# osuar_pdb.net
KiCad netlist of a schematic drawn in EAGLE
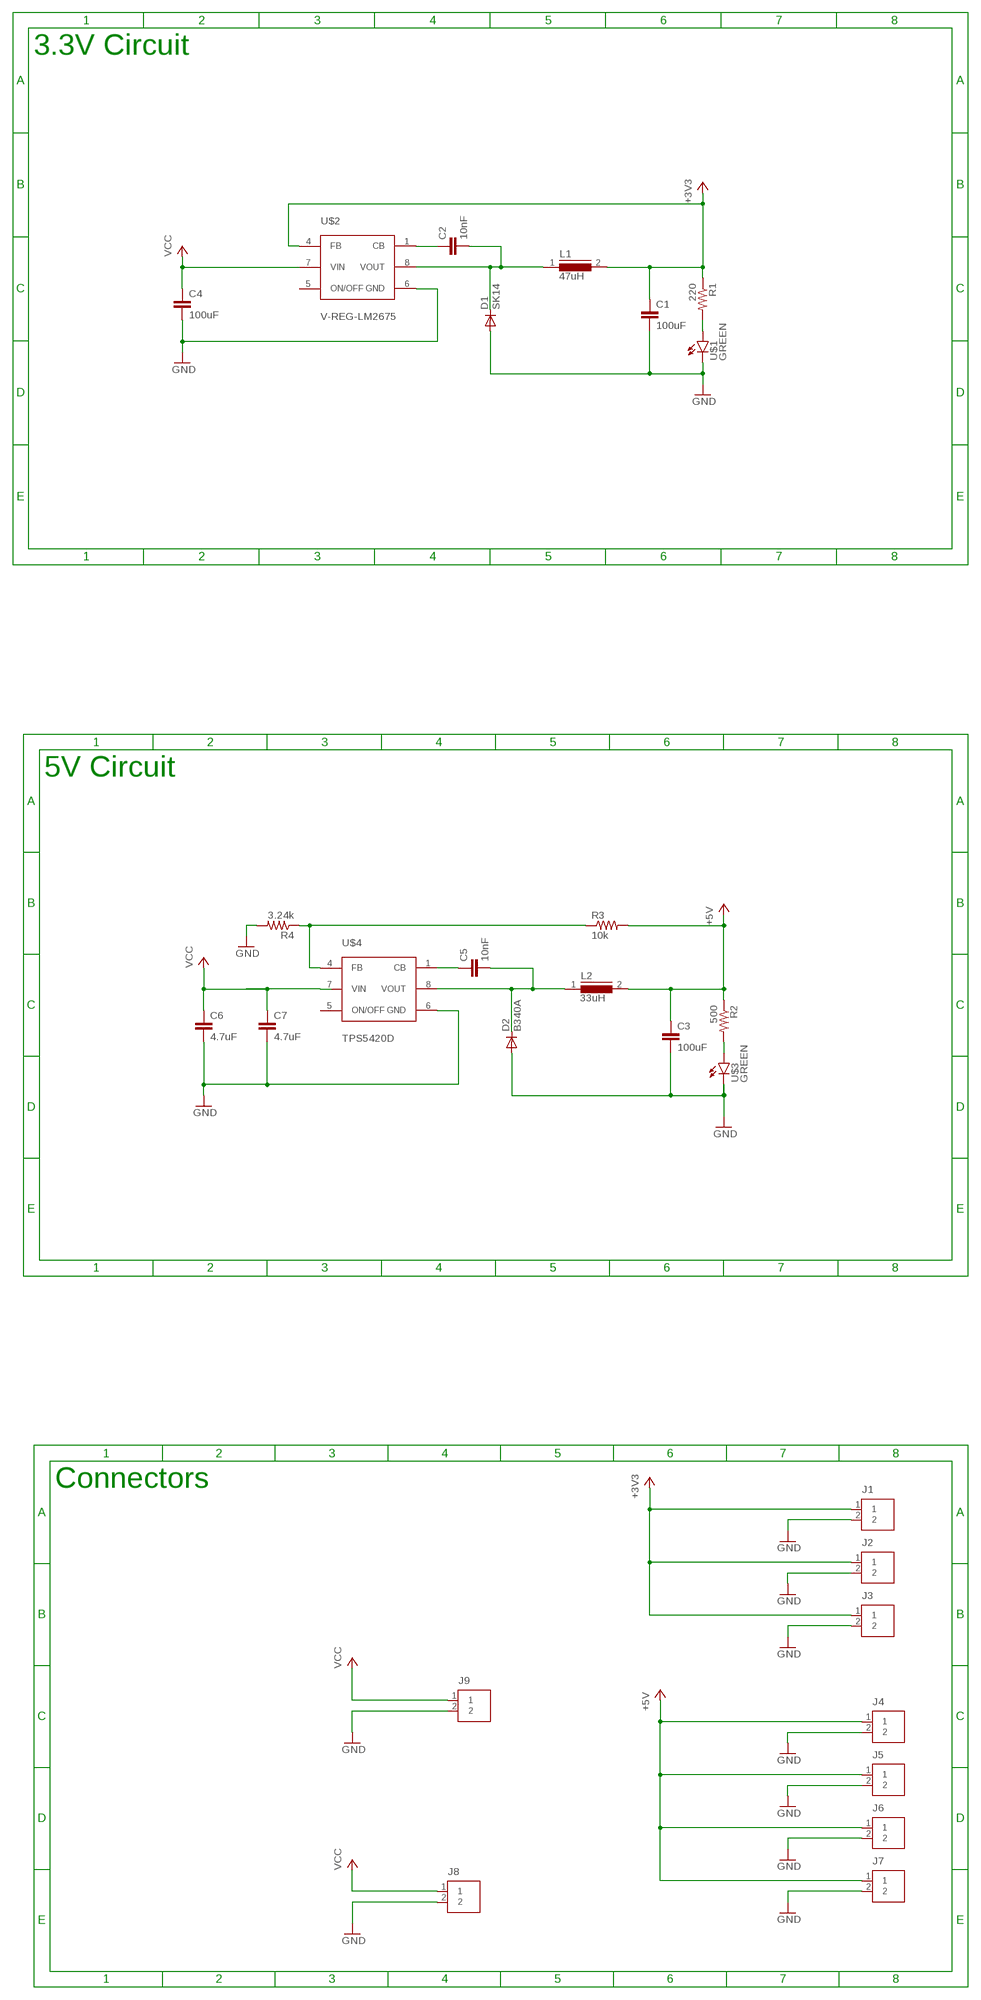
[diagram p0: schematic, sheet 1]

(export (version "E")
  (design (tool "Eeschema 10.0.6"))
  (components
    (comp (ref "C1")
      (value "100uF")
      (footprint "eagle-import:0805")
      (libsource (lib "eagle-import") (part "CAP-10UF-10V-10%(0805)"))
    )
    (comp (ref "C2")
      (value "10nF")
      (footprint "eagle-import:0603")
      (libsource (lib "eagle-import") (part "CAP-10NF-50V-10%(0603)"))
    )
    (comp (ref "C3")
      (value "100uF")
      (footprint "eagle-import:0805")
      (libsource (lib "eagle-import") (part "CAP-10UF-10V-10%(0805)"))
    )
    (comp (ref "C4")
      (value "100uF")
      (footprint "eagle-import:0805")
      (libsource (lib "eagle-import") (part "CAP-10UF-10V-10%(0805)"))
    )
    (comp (ref "C5")
      (value "10nF")
      (footprint "eagle-import:0603")
      (libsource (lib "eagle-import") (part "CAP-10NF-50V-10%(0603)"))
    )
    (comp (ref "C6")
      (value "4.7uF")
      (footprint "eagle-import:0805")
      (libsource (lib "eagle-import") (part "CAP-10UF-10V-10%(0805)"))
    )
    (comp (ref "C7")
      (value "4.7uF")
      (footprint "eagle-import:0805")
      (libsource (lib "eagle-import") (part "CAP-10UF-10V-10%(0805)"))
    )
    (comp (ref "D1")
      (value "SK14")
      (footprint "eagle-import:DO214AA")
      (libsource (lib "eagle-import") (part "DIODE-DO214AA"))
    )
    (comp (ref "D2")
      (value "B340A")
      (footprint "eagle-import:DO214AA")
      (libsource (lib "eagle-import") (part "DIODE-DO214AA"))
    )
    (comp (ref "J1")
      (value "M02")
      (footprint "eagle-import:MOLEX-2MM-MICROLATCH-2POS-RA")
      (libsource (lib "eagle-import") (part "M02"))
    )
    (comp (ref "J2")
      (value "M02")
      (footprint "eagle-import:MOLEX-2MM-MICROLATCH-2POS-RA")
      (libsource (lib "eagle-import") (part "M02"))
    )
    (comp (ref "J3")
      (value "M02")
      (footprint "eagle-import:MOLEX-2MM-MICROLATCH-2POS-RA")
      (libsource (lib "eagle-import") (part "M02"))
    )
    (comp (ref "J4")
      (value "M02")
      (footprint "eagle-import:MOLEX-2MM-MICROLATCH-2POS-RA")
      (libsource (lib "eagle-import") (part "M02"))
    )
    (comp (ref "J5")
      (value "M02")
      (footprint "eagle-import:MOLEX-2MM-MICROLATCH-2POS-RA")
      (libsource (lib "eagle-import") (part "M02"))
    )
    (comp (ref "J6")
      (value "M02")
      (footprint "eagle-import:MOLEX-2MM-MICROLATCH-2POS-RA")
      (libsource (lib "eagle-import") (part "M02"))
    )
    (comp (ref "J7")
      (value "M02")
      (footprint "eagle-import:MOLEX-2MM-MICROLATCH-2POS-RA")
      (libsource (lib "eagle-import") (part "M02"))
    )
    (comp (ref "J8")
      (value "M02")
      (footprint "eagle-import:MOLEX-2MM-MICROLATCH-2POS-RA")
      (libsource (lib "eagle-import") (part "M02"))
    )
    (comp (ref "J9")
      (value "M02")
      (footprint "eagle-import:MOLEX-2MM-MICROLATCH-2POS-RA")
      (libsource (lib "eagle-import") (part "M02"))
    )
    (comp (ref "L1")
      (value "47uH")
      (footprint "eagle-import:DR125")
      (libsource (lib "eagle-import") (part "DR125"))
    )
    (comp (ref "L2")
      (value "33uH")
      (footprint "eagle-import:DR125")
      (libsource (lib "eagle-import") (part "DR125"))
    )
    (comp (ref "R1")
      (value "220")
      (footprint "eagle-import:0603")
      (libsource (lib "eagle-import") (part "RES-1.1KOHM-0.1W-5%(0603)"))
    )
    (comp (ref "R2")
      (value "500")
      (footprint "eagle-import:0603")
      (libsource (lib "eagle-import") (part "RES-1.1KOHM-0.1W-5%(0603)"))
    )
    (comp (ref "R3")
      (value "10k")
      (footprint "eagle-import:0603")
      (libsource (lib "eagle-import") (part "RES-20KOHM-0.1W-0.1%(0603)"))
    )
    (comp (ref "R4")
      (value "3.24k")
      (footprint "eagle-import:0603")
      (libsource (lib "eagle-import") (part "RES-20KOHM-0.1W-0.1%(0603)"))
    )
    (comp (ref "U$1")
      (value "GREEN")
      (footprint "eagle-import:LED-0603")
      (libsource (lib "eagle-import") (part "LED-KINGBRIGHT-HELI-GREEN(0603)"))
    )
    (comp (ref "U$2")
      (value "V-REG-LM2675")
      (footprint "eagle-import:SOIC8")
      (libsource (lib "eagle-import") (part "V-REG-LM2675"))
    )
    (comp (ref "U$3")
      (value "GREEN")
      (footprint "eagle-import:LED-0603")
      (libsource (lib "eagle-import") (part "LED-KINGBRIGHT-HELI-GREEN(0603)"))
    )
    (comp (ref "U$4")
      (value "TPS5420D")
      (footprint "eagle-import:SOIC8")
      (libsource (lib "eagle-import") (part "V-REG-TPS5420D"))
    )
  )
  (nets
    (net (code "1") (name "+3V3") (class "Default")
      (node (ref "C1") (pin "2") (pinfunction "2_2") (pintype "passive"))
      (node (ref "J1") (pin "1") (pinfunction "1_1") (pintype "bidirectional"))
      (node (ref "J2") (pin "1") (pinfunction "1_1") (pintype "bidirectional"))
      (node (ref "J3") (pin "1") (pinfunction "1_1") (pintype "bidirectional"))
      (node (ref "L1") (pin "2") (pinfunction "2_2") (pintype "passive"))
      (node (ref "R1") (pin "1") (pinfunction "1_1") (pintype "passive"))
      (node (ref "U$2") (pin "4") (pinfunction "FB_4") (pintype "input"))
    )
    (net (code "2") (name "+5V") (class "Default")
      (node (ref "C3") (pin "2") (pinfunction "2_2") (pintype "passive"))
      (node (ref "J4") (pin "1") (pinfunction "1_1") (pintype "bidirectional"))
      (node (ref "J5") (pin "1") (pinfunction "1_1") (pintype "bidirectional"))
      (node (ref "J6") (pin "1") (pinfunction "1_1") (pintype "bidirectional"))
      (node (ref "J7") (pin "1") (pinfunction "1_1") (pintype "bidirectional"))
      (node (ref "L2") (pin "2") (pinfunction "2_2") (pintype "passive"))
      (node (ref "R2") (pin "1") (pinfunction "1_1") (pintype "passive"))
      (node (ref "R3") (pin "2") (pinfunction "2_2") (pintype "passive"))
    )
    (net (code "3") (name "GND") (class "Default")
      (node (ref "C1") (pin "1") (pinfunction "1_1") (pintype "passive"))
      (node (ref "C3") (pin "1") (pinfunction "1_1") (pintype "passive"))
      (node (ref "C4") (pin "1") (pinfunction "1_1") (pintype "passive"))
      (node (ref "C6") (pin "1") (pinfunction "1_1") (pintype "passive"))
      (node (ref "C7") (pin "1") (pinfunction "1_1") (pintype "passive"))
      (node (ref "D1") (pin "A") (pinfunction "A_A") (pintype "passive"))
      (node (ref "D2") (pin "A") (pinfunction "A_A") (pintype "passive"))
      (node (ref "J1") (pin "2") (pinfunction "2_2") (pintype "bidirectional"))
      (node (ref "J2") (pin "2") (pinfunction "2_2") (pintype "bidirectional"))
      (node (ref "J3") (pin "2") (pinfunction "2_2") (pintype "bidirectional"))
      (node (ref "J4") (pin "2") (pinfunction "2_2") (pintype "bidirectional"))
      (node (ref "J5") (pin "2") (pinfunction "2_2") (pintype "bidirectional"))
      (node (ref "J6") (pin "2") (pinfunction "2_2") (pintype "bidirectional"))
      (node (ref "J7") (pin "2") (pinfunction "2_2") (pintype "bidirectional"))
      (node (ref "J8") (pin "2") (pinfunction "2_2") (pintype "bidirectional"))
      (node (ref "J9") (pin "2") (pinfunction "2_2") (pintype "bidirectional"))
      (node (ref "R4") (pin "2") (pinfunction "2_2") (pintype "passive"))
      (node (ref "U$1") (pin "C") (pinfunction "C_C") (pintype "passive"))
      (node (ref "U$2") (pin "6") (pinfunction "GND_6") (pintype "power_in"))
      (node (ref "U$3") (pin "C") (pinfunction "C_C") (pintype "passive"))
      (node (ref "U$4") (pin "6") (pinfunction "GND_6") (pintype "power_in"))
    )
    (net (code "4") (name "Net-(R1-Pad2)") (class "Default")
      (node (ref "R1") (pin "2") (pinfunction "2_2") (pintype "passive"))
      (node (ref "U$1") (pin "A") (pinfunction "A_A") (pintype "passive"))
    )
    (net (code "5") (name "Net-(R2-Pad2)") (class "Default")
      (node (ref "R2") (pin "2") (pinfunction "2_2") (pintype "passive"))
      (node (ref "U$3") (pin "A") (pinfunction "A_A") (pintype "passive"))
    )
    (net (code "6") (name "Net-(U$2-CB)") (class "Default")
      (node (ref "C2") (pin "2") (pinfunction "2_2") (pintype "passive"))
      (node (ref "U$2") (pin "1") (pinfunction "CB_1") (pintype "input"))
    )
    (net (code "7") (name "Net-(U$2-VOUT)") (class "Default")
      (node (ref "C2") (pin "1") (pinfunction "1_1") (pintype "passive"))
      (node (ref "D1") (pin "C") (pinfunction "C_C") (pintype "passive"))
      (node (ref "L1") (pin "1") (pinfunction "1_1") (pintype "passive"))
      (node (ref "U$2") (pin "8") (pinfunction "VOUT_8") (pintype "output"))
    )
    (net (code "8") (name "Net-(U$4-CB)") (class "Default")
      (node (ref "C5") (pin "2") (pinfunction "2_2") (pintype "passive"))
      (node (ref "U$4") (pin "1") (pinfunction "CB_1") (pintype "input"))
    )
    (net (code "9") (name "Net-(U$4-FB)") (class "Default")
      (node (ref "R3") (pin "1") (pinfunction "1_1") (pintype "passive"))
      (node (ref "R4") (pin "1") (pinfunction "1_1") (pintype "passive"))
      (node (ref "U$4") (pin "4") (pinfunction "FB_4") (pintype "input"))
    )
    (net (code "10") (name "Net-(U$4-VOUT)") (class "Default")
      (node (ref "C5") (pin "1") (pinfunction "1_1") (pintype "passive"))
      (node (ref "D2") (pin "C") (pinfunction "C_C") (pintype "passive"))
      (node (ref "L2") (pin "1") (pinfunction "1_1") (pintype "passive"))
      (node (ref "U$4") (pin "8") (pinfunction "VOUT_8") (pintype "output"))
    )
    (net (code "11") (name "VCC") (class "Default")
      (node (ref "C4") (pin "2") (pinfunction "2_2") (pintype "passive"))
      (node (ref "C6") (pin "2") (pinfunction "2_2") (pintype "passive"))
      (node (ref "C7") (pin "2") (pinfunction "2_2") (pintype "passive"))
      (node (ref "J8") (pin "1") (pinfunction "1_1") (pintype "bidirectional"))
      (node (ref "J9") (pin "1") (pinfunction "1_1") (pintype "bidirectional"))
      (node (ref "U$2") (pin "7") (pinfunction "VIN_7") (pintype "input"))
      (node (ref "U$4") (pin "7") (pinfunction "VIN_7") (pintype "input"))
    )
    (net (code "12") (name "unconnected-(U$2-ON{slash}OFF-Pad5)") (class "Default")
      (node (ref "U$2") (pin "5") (pinfunction "ON/OFF_5") (pintype "no_connect"))
    )
    (net (code "13") (name "unconnected-(U$4-ON{slash}OFF-Pad5)") (class "Default")
      (node (ref "U$4") (pin "5") (pinfunction "ON/OFF_5") (pintype "no_connect"))
    )
  )
)
